# ftdiBreakout.net
KiCad netlist of a schematic drawn in EAGLE
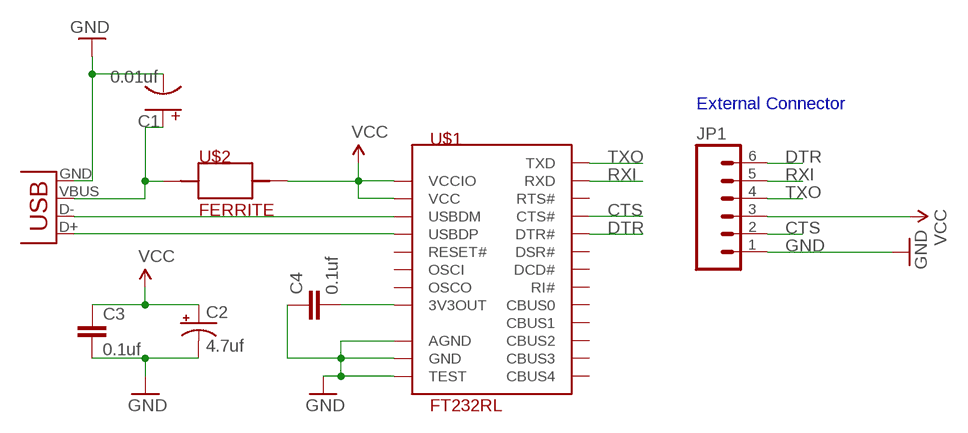
[diagram p0: schematic, sheet 1]

(export (version "E")
  (design (tool "Eeschema 10.0.6"))
  (components
    (comp (ref "C1")
      (value "0.01uf")
      (footprint "eagle-import:0805POL")
      (libsource (lib "eagle-import") (part "CAP_POL"))
    )
    (comp (ref "C2")
      (value "4.7uf")
      (footprint "eagle-import:CPOL-RADIAL-100UF-25V")
      (libsource (lib "eagle-import") (part "CAP_POLPTH1"))
    )
    (comp (ref "C3")
      (value "0.1uf")
      (footprint "eagle-import:0805")
      (libsource (lib "eagle-import") (part "CAP0805"))
    )
    (comp (ref "C4")
      (value "0.1uf")
      (footprint "eagle-import:0805")
      (libsource (lib "eagle-import") (part "CAP0805"))
    )
    (comp (ref "JP1")
      (value "M06SIP")
      (footprint "eagle-import:1X06")
      (libsource (lib "eagle-import") (part "M06SIP"))
    )
    (comp (ref "U$1")
      (value "FT232RL")
      (footprint "eagle-import:TSSOP28")
      (libsource (lib "eagle-import") (part "FT232RL"))
    )
    (comp (ref "U$2")
      (value "FERRITE")
      (footprint "eagle-import:0805")
      (libsource (lib "eagle-import") (part "FERRITE"))
    )
    (comp (ref "X1")
      (value "USBSMD")
      (footprint "eagle-import:USB-MINIB")
      (libsource (lib "eagle-import") (part "USBSMD"))
    )
  )
  (nets
    (net (code "1") (name "/CTS") (class "Default")
      (node (ref "JP1") (pin "2") (pinfunction "2_2") (pintype "passive"))
      (node (ref "U$1") (pin "11") (pinfunction "CTS#_11") (pintype "bidirectional"))
    )
    (net (code "2") (name "/DTR") (class "Default")
      (node (ref "JP1") (pin "6") (pinfunction "6_6") (pintype "passive"))
      (node (ref "U$1") (pin "2") (pinfunction "DTR#_2") (pintype "bidirectional"))
    )
    (net (code "3") (name "/RXI") (class "Default")
      (node (ref "JP1") (pin "5") (pinfunction "5_5") (pintype "passive"))
      (node (ref "U$1") (pin "5") (pinfunction "RXD_5") (pintype "bidirectional"))
    )
    (net (code "4") (name "/TXO") (class "Default")
      (node (ref "JP1") (pin "4") (pinfunction "4_4") (pintype "passive"))
      (node (ref "U$1") (pin "1") (pinfunction "TXD_1") (pintype "bidirectional"))
    )
    (net (code "5") (name "GND") (class "Default")
      (node (ref "C1") (pin "-") (pinfunction "-_-") (pintype "bidirectional"))
      (node (ref "C2") (pin "2") (pinfunction "-_2") (pintype "passive"))
      (node (ref "C3") (pin "2") (pinfunction "2_2") (pintype "passive"))
      (node (ref "C4") (pin "1") (pinfunction "1_1") (pintype "passive"))
      (node (ref "JP1") (pin "1") (pinfunction "1_1") (pintype "passive"))
      (node (ref "U$1") (pin "18") (pinfunction "GND_18") (pintype "bidirectional"))
      (node (ref "U$1") (pin "21") (pinfunction "GND_21") (pintype "bidirectional"))
      (node (ref "U$1") (pin "25") (pinfunction "AGND_25") (pintype "bidirectional"))
      (node (ref "U$1") (pin "26") (pinfunction "TEST_26") (pintype "bidirectional"))
      (node (ref "U$1") (pin "7") (pinfunction "GND_7") (pintype "bidirectional"))
      (node (ref "X1") (pin "GND") (pinfunction "GND_GND") (pintype "bidirectional"))
    )
    (net (code "6") (name "Net-(U$1-3V3OUT)") (class "Default")
      (node (ref "C4") (pin "2") (pinfunction "2_2") (pintype "passive"))
      (node (ref "U$1") (pin "17") (pinfunction "3V3OUT_17") (pintype "bidirectional"))
    )
    (net (code "7") (name "Net-(U$1-USBDM)") (class "Default")
      (node (ref "U$1") (pin "16") (pinfunction "USBDM_16") (pintype "bidirectional"))
      (node (ref "X1") (pin "D-") (pinfunction "D-_D-") (pintype "bidirectional"))
    )
    (net (code "8") (name "Net-(U$1-USBDP)") (class "Default")
      (node (ref "U$1") (pin "15") (pinfunction "USBDP_15") (pintype "bidirectional"))
      (node (ref "X1") (pin "D+") (pinfunction "D+_D+") (pintype "bidirectional"))
    )
    (net (code "9") (name "Net-(U$2-P$1)") (class "Default")
      (node (ref "C1") (pin "+") (pinfunction "+_+") (pintype "bidirectional"))
      (node (ref "U$2") (pin "1") (pinfunction "P$1_1") (pintype "bidirectional"))
      (node (ref "X1") (pin "VBUS") (pinfunction "VBUS_VBUS") (pintype "bidirectional"))
    )
    (net (code "10") (name "VCC") (class "Default")
      (node (ref "C2") (pin "1") (pinfunction "+_1") (pintype "passive"))
      (node (ref "C3") (pin "1") (pinfunction "1_1") (pintype "passive"))
      (node (ref "JP1") (pin "3") (pinfunction "3_3") (pintype "passive"))
      (node (ref "U$1") (pin "20") (pinfunction "VCC_20") (pintype "bidirectional"))
      (node (ref "U$1") (pin "4") (pinfunction "VCCIO_4") (pintype "bidirectional"))
      (node (ref "U$2") (pin "2") (pinfunction "P$2_2") (pintype "bidirectional"))
    )
    (net (code "11") (name "unconnected-(U$1-CBUS0-Pad23)") (class "Default")
      (node (ref "U$1") (pin "23") (pinfunction "CBUS0_23") (pintype "bidirectional"))
    )
    (net (code "12") (name "unconnected-(U$1-CBUS1-Pad22)") (class "Default")
      (node (ref "U$1") (pin "22") (pinfunction "CBUS1_22") (pintype "bidirectional"))
    )
    (net (code "13") (name "unconnected-(U$1-CBUS2-Pad13)") (class "Default")
      (node (ref "U$1") (pin "13") (pinfunction "CBUS2_13") (pintype "bidirectional"))
    )
    (net (code "14") (name "unconnected-(U$1-CBUS3-Pad14)") (class "Default")
      (node (ref "U$1") (pin "14") (pinfunction "CBUS3_14") (pintype "bidirectional"))
    )
    (net (code "15") (name "unconnected-(U$1-CBUS4-Pad12)") (class "Default")
      (node (ref "U$1") (pin "12") (pinfunction "CBUS4_12") (pintype "bidirectional"))
    )
    (net (code "16") (name "unconnected-(U$1-DCD#-Pad10)") (class "Default")
      (node (ref "U$1") (pin "10") (pinfunction "DCD#_10") (pintype "bidirectional"))
    )
    (net (code "17") (name "unconnected-(U$1-DSR#-Pad9)") (class "Default")
      (node (ref "U$1") (pin "9") (pinfunction "DSR#_9") (pintype "bidirectional"))
    )
    (net (code "18") (name "unconnected-(U$1-OSCI-Pad27)") (class "Default")
      (node (ref "U$1") (pin "27") (pinfunction "OSCI_27") (pintype "bidirectional"))
    )
    (net (code "19") (name "unconnected-(U$1-OSCO-Pad28)") (class "Default")
      (node (ref "U$1") (pin "28") (pinfunction "OSCO_28") (pintype "bidirectional"))
    )
    (net (code "20") (name "unconnected-(U$1-RESET#-Pad19)") (class "Default")
      (node (ref "U$1") (pin "19") (pinfunction "RESET#_19") (pintype "bidirectional"))
    )
    (net (code "21") (name "unconnected-(U$1-RI#-Pad6)") (class "Default")
      (node (ref "U$1") (pin "6") (pinfunction "RI#_6") (pintype "bidirectional"))
    )
    (net (code "22") (name "unconnected-(U$1-RTS#-Pad3)") (class "Default")
      (node (ref "U$1") (pin "3") (pinfunction "RTS#_3") (pintype "bidirectional"))
    )
  )
)
